# BatteryMQTTSense.net
KiCad netlist of a schematic drawn in EAGLE
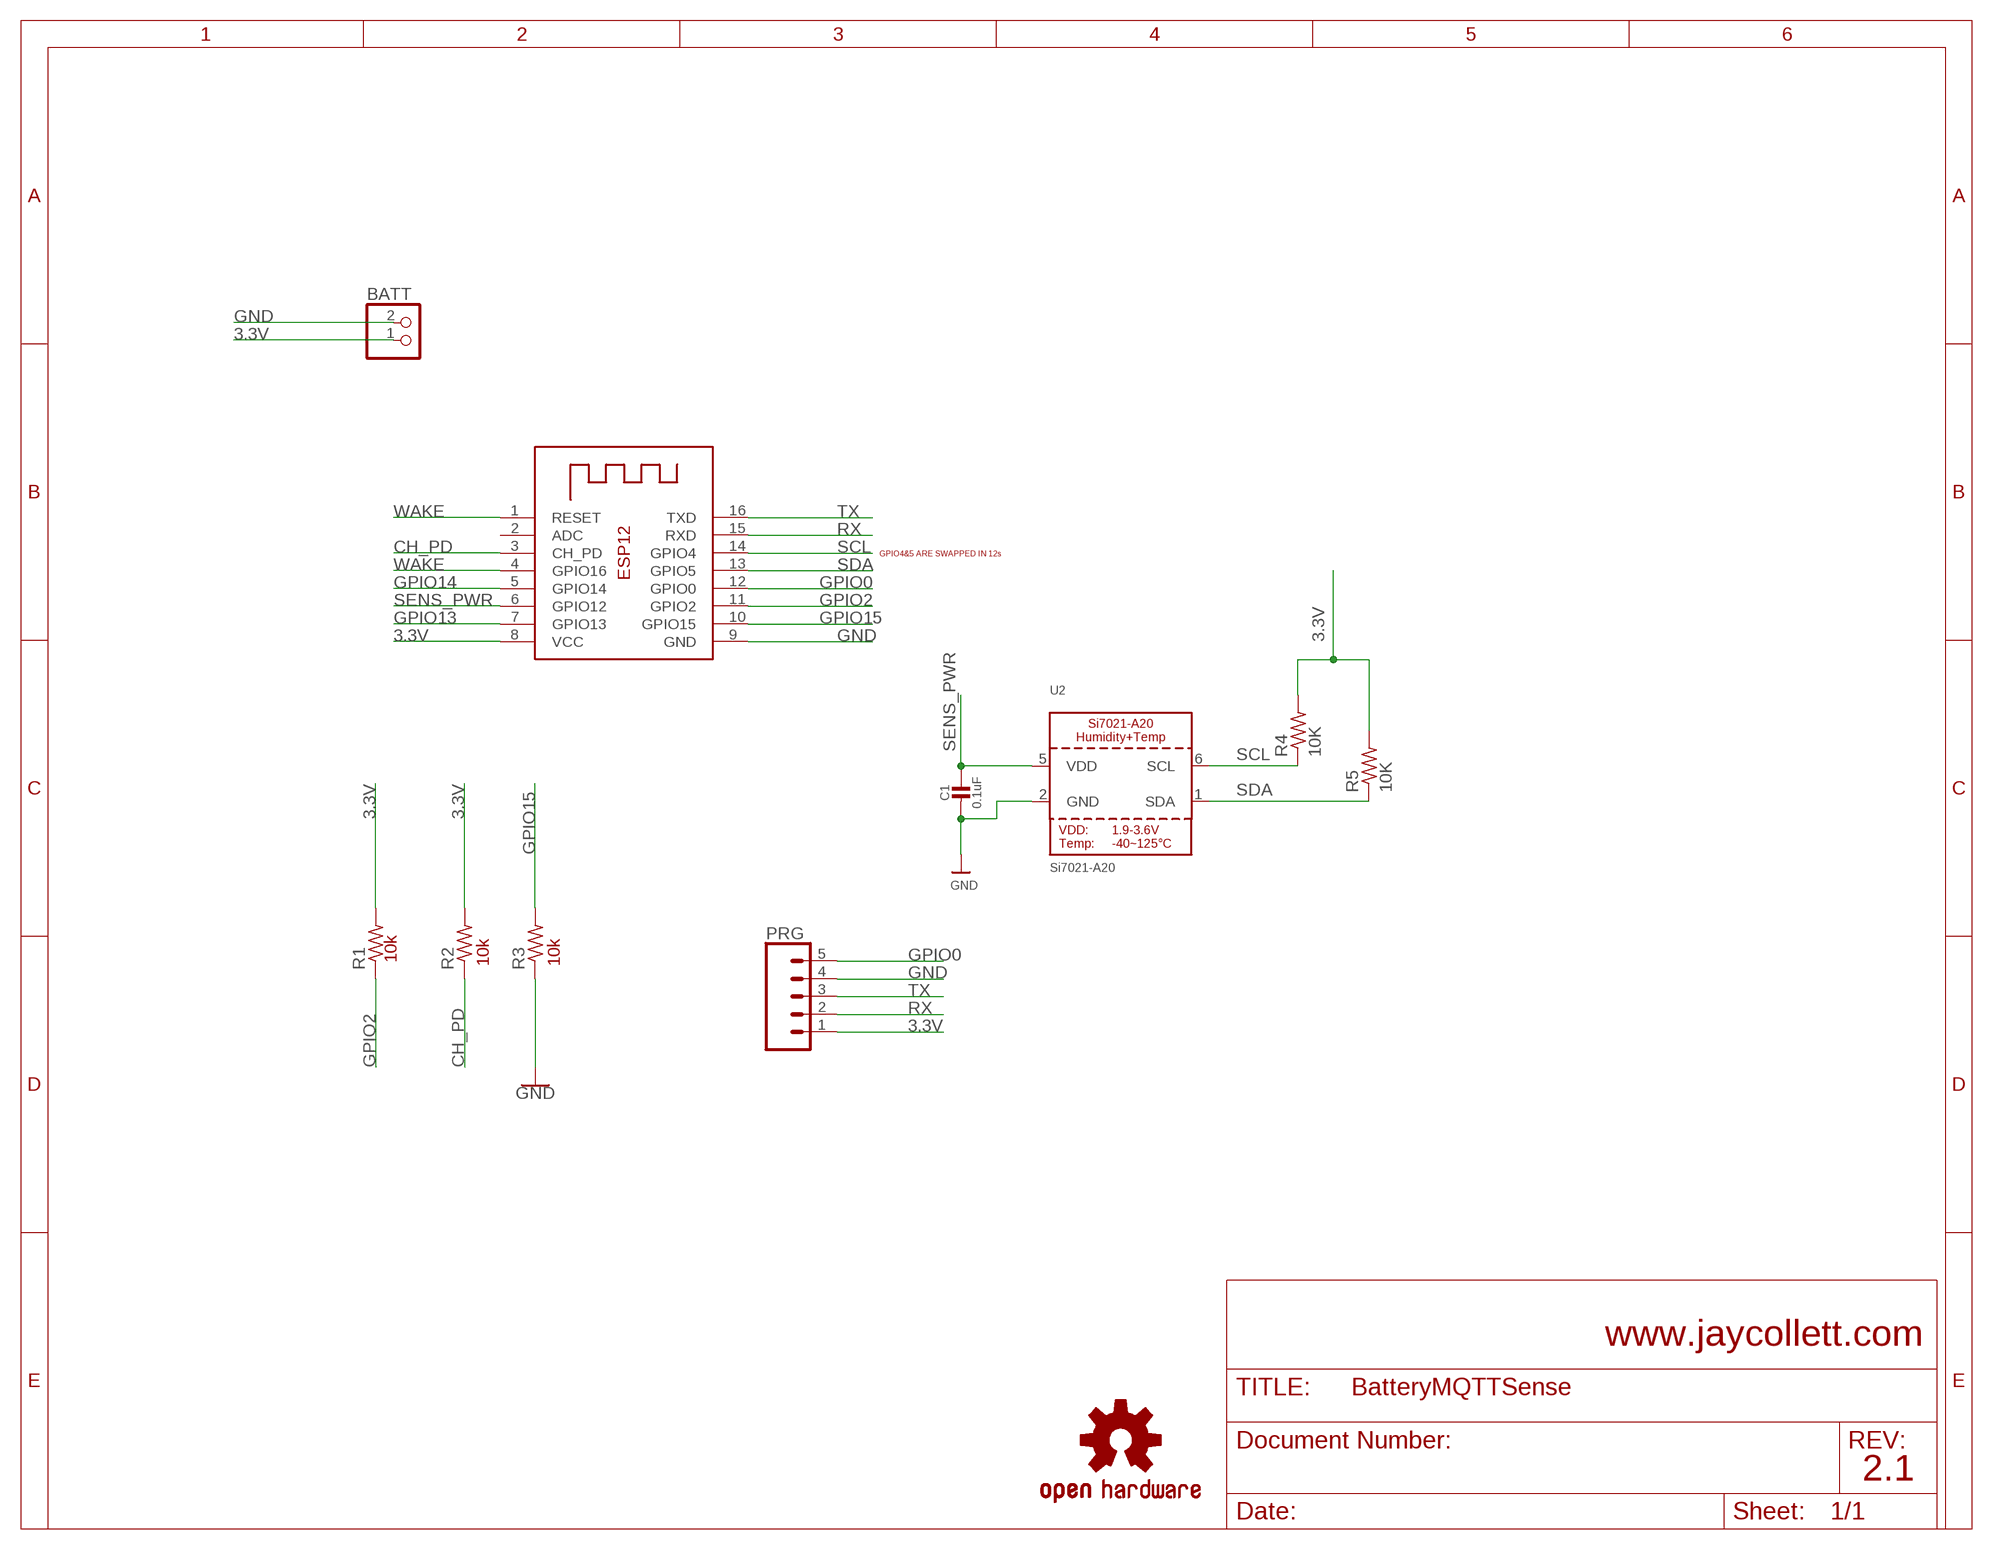
[diagram p0: schematic, sheet 1]

(export (version "E")
  (design (tool "Eeschema 10.0.6"))
  (components
    (comp (ref "BATT")
      (value "JST_2PIN-THM-RA")
      (footprint "eagle-import:JST-PH-2-THM-RA")
      (libsource (lib "eagle-import") (part "JST_2PIN-THM-RA"))
    )
    (comp (ref "C1")
      (value "0.1uF")
      (footprint "eagle-import:0805-NO")
      (libsource (lib "eagle-import") (part "CAP_CERAMIC0805-NOOUTLINE"))
    )
    (comp (ref "LOGO1")
      (value "OSHW-LOGOS")
      (footprint "eagle-import:OSHW-LOGO-S")
      (libsource (lib "eagle-import") (part "OSHW-LOGOS"))
    )
    (comp (ref "PRG")
      (value "CONN_05PTH_LONGPADS")
      (footprint "eagle-import:1X05_LONGPADS")
      (libsource (lib "eagle-import") (part "CONN_05PTH_LONGPADS"))
    )
    (comp (ref "R1")
      (value "R-US_M0805")
      (footprint "eagle-import:M0805")
      (libsource (lib "eagle-import") (part "R-US_M0805"))
    )
    (comp (ref "R2")
      (value "R-US_M0805")
      (footprint "eagle-import:M0805")
      (libsource (lib "eagle-import") (part "R-US_M0805"))
    )
    (comp (ref "R3")
      (value "R-US_M0805")
      (footprint "eagle-import:M0805")
      (libsource (lib "eagle-import") (part "R-US_M0805"))
    )
    (comp (ref "R4")
      (value "10K")
      (footprint "eagle-import:M0805")
      (libsource (lib "eagle-import") (part "R-US_M0805"))
    )
    (comp (ref "R5")
      (value "10K")
      (footprint "eagle-import:M0805")
      (libsource (lib "eagle-import") (part "R-US_M0805"))
    )
    (comp (ref "U2")
      (value "Si7021-A20")
      (footprint "eagle-import:DFN6_3X3_SI")
      (libsource (lib "eagle-import") (part "SI7021-A20"))
    )
    (comp (ref "_")
      (value "ESP-12")
      (footprint "eagle-import:ESP-12")
      (libsource (lib "eagle-import") (part "ESP-12"))
    )
  )
  (nets
    (net (code "1") (name "/3.3V") (class "Default")
      (node (ref "BATT") (pin "1") (pinfunction "2_1") (pintype "passive"))
      (node (ref "PRG") (pin "1") (pinfunction "1_1") (pintype "passive"))
      (node (ref "R1") (pin "2") (pinfunction "2_2") (pintype "passive"))
      (node (ref "R2") (pin "2") (pinfunction "2_2") (pintype "passive"))
      (node (ref "R4") (pin "2") (pinfunction "2_2") (pintype "passive"))
      (node (ref "R5") (pin "2") (pinfunction "2_2") (pintype "passive"))
      (node (ref "_") (pin "8") (pinfunction "VCC_8") (pintype "power_in"))
    )
    (net (code "2") (name "/CH_PD") (class "Default")
      (node (ref "R2") (pin "1") (pinfunction "1_1") (pintype "passive"))
      (node (ref "_") (pin "3") (pinfunction "CH_PD_3") (pintype "input"))
    )
    (net (code "3") (name "/GPIO0") (class "Default")
      (node (ref "PRG") (pin "5") (pinfunction "5_5") (pintype "passive"))
      (node (ref "_") (pin "12") (pinfunction "GPIO0_12") (pintype "bidirectional"))
    )
    (net (code "4") (name "/GPIO2") (class "Default")
      (node (ref "R1") (pin "1") (pinfunction "1_1") (pintype "passive"))
      (node (ref "_") (pin "11") (pinfunction "GPIO2_11") (pintype "bidirectional"))
    )
    (net (code "5") (name "/GPIO13") (class "Default")
      (node (ref "_") (pin "7") (pinfunction "GPIO13_7") (pintype "bidirectional"))
    )
    (net (code "6") (name "/GPIO14") (class "Default")
      (node (ref "_") (pin "5") (pinfunction "GPIO14_5") (pintype "bidirectional"))
    )
    (net (code "7") (name "/GPIO15") (class "Default")
      (node (ref "R3") (pin "2") (pinfunction "2_2") (pintype "passive"))
      (node (ref "_") (pin "10") (pinfunction "GPIO15_10") (pintype "bidirectional"))
    )
    (net (code "8") (name "/RX") (class "Default")
      (node (ref "PRG") (pin "2") (pinfunction "2_2") (pintype "passive"))
      (node (ref "_") (pin "15") (pinfunction "RXD_15") (pintype "input"))
    )
    (net (code "9") (name "/SCL") (class "Default")
      (node (ref "R4") (pin "1") (pinfunction "1_1") (pintype "passive"))
      (node (ref "U2") (pin "6") (pinfunction "SCL_6") (pintype "open_collector"))
      (node (ref "_") (pin "14") (pinfunction "GPIO4_14") (pintype "bidirectional"))
    )
    (net (code "10") (name "/SDA") (class "Default")
      (node (ref "R5") (pin "1") (pinfunction "1_1") (pintype "passive"))
      (node (ref "U2") (pin "1") (pinfunction "SDA_1") (pintype "open_collector"))
      (node (ref "_") (pin "13") (pinfunction "GPIO5_13") (pintype "bidirectional"))
    )
    (net (code "11") (name "/SENS_PWR") (class "Default")
      (node (ref "C1") (pin "1") (pinfunction "1_1") (pintype "passive"))
      (node (ref "U2") (pin "5") (pinfunction "VDD_5") (pintype "power_in"))
      (node (ref "_") (pin "6") (pinfunction "GPIO12_6") (pintype "bidirectional"))
    )
    (net (code "12") (name "/TX") (class "Default")
      (node (ref "PRG") (pin "3") (pinfunction "3_3") (pintype "passive"))
      (node (ref "_") (pin "16") (pinfunction "TXD_16") (pintype "output"))
    )
    (net (code "13") (name "/WAKE") (class "Default")
      (node (ref "_") (pin "1") (pinfunction "RESET_1") (pintype "input"))
      (node (ref "_") (pin "4") (pinfunction "GPIO16_4") (pintype "bidirectional"))
    )
    (net (code "14") (name "GND") (class "Default")
      (node (ref "BATT") (pin "2") (pinfunction "1_2") (pintype "passive"))
      (node (ref "C1") (pin "2") (pinfunction "2_2") (pintype "passive"))
      (node (ref "PRG") (pin "4") (pinfunction "4_4") (pintype "passive"))
      (node (ref "R3") (pin "1") (pinfunction "1_1") (pintype "passive"))
      (node (ref "U2") (pin "2") (pinfunction "GND_2") (pintype "power_in"))
      (node (ref "_") (pin "9") (pinfunction "GND_9") (pintype "power_in"))
    )
    (net (code "15") (name "unconnected-(_-ADC-Pad2)") (class "Default")
      (node (ref "_") (pin "2") (pinfunction "ADC_2") (pintype "passive"))
    )
  )
)
